# Doorbell.net
KiCad netlist of a schematic drawn in EAGLE
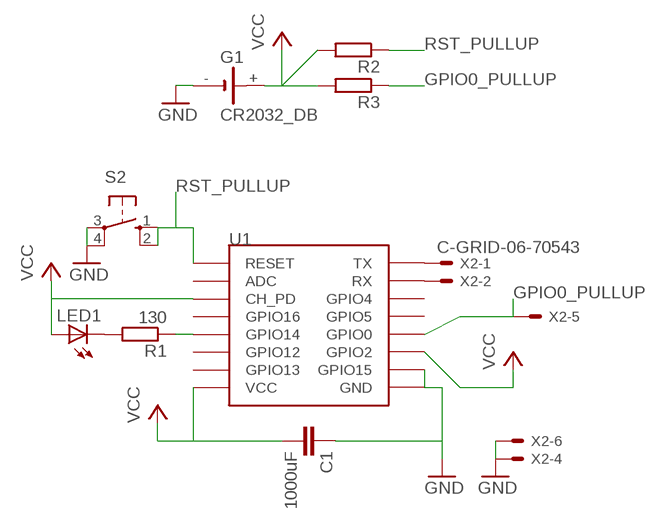
[diagram p0: schematic, sheet 1]

(export (version "E")
  (design (tool "Eeschema 10.0.6"))
  (components
    (comp (ref "C1")
      (value "1000uF")
      (footprint "eagle-import:C5B3.5")
      (libsource (lib "eagle-import") (part "C5/3.5"))
    )
    (comp (ref "G1")
      (value "CR2032_DB")
      (footprint "eagle-import:CR2032_DOORBELL")
      (libsource (lib "eagle-import") (part "CR2032_DB"))
    )
    (comp (ref "LED1")
      (value "LED3MM")
      (footprint "eagle-import:LED3MM")
      (libsource (lib "eagle-import") (part "LED3MM"))
    )
    (comp (ref "R1")
      (value "130")
      (footprint "eagle-import:0204_5")
      (libsource (lib "eagle-import") (part "R-EU_0204/5"))
    )
    (comp (ref "R2")
      (value "R-EU_0204/5")
      (footprint "eagle-import:0204_5")
      (libsource (lib "eagle-import") (part "R-EU_0204/5"))
    )
    (comp (ref "R3")
      (value "R-EU_0204/5")
      (footprint "eagle-import:0204_5")
      (libsource (lib "eagle-import") (part "R-EU_0204/5"))
    )
    (comp (ref "S2")
      (value "10-XX")
      (footprint "eagle-import:B3F-10XX")
      (fields (field (name "MPN") "B3F-1000"))
      (libsource (lib "eagle-import") (part "10-XX"))
    )
    (comp (ref "U1")
      (value "ESP12")
      (footprint "eagle-import:ESP12")
      (libsource (lib "eagle-import") (part "ESP12"))
    )
    (comp (ref "X2")
      (value "C-GRID-06-70543")
      (footprint "eagle-import:70543-06")
      (libsource (lib "eagle-import") (part "C-GRID-06-70543"))
    )
  )
  (nets
    (net (code "1") (name "/GPIO0_PULLUP") (class "Default")
      (node (ref "R3") (pin "1") (pinfunction "1_1") (pintype "passive"))
      (node (ref "U1") (pin "GPIO0") (pinfunction "GPIO0_GPIO0") (pintype "bidirectional"))
      (node (ref "X2") (pin "5") (pinfunction "S_5") (pintype "passive"))
    )
    (net (code "2") (name "/RST_PULLUP") (class "Default")
      (node (ref "R2") (pin "1") (pinfunction "1_1") (pintype "passive"))
      (node (ref "S2") (pin "1") (pinfunction "S_1") (pintype "passive"))
      (node (ref "S2") (pin "2") (pinfunction "S1_2") (pintype "passive"))
      (node (ref "U1") (pin "RESET") (pinfunction "RESET_RESET") (pintype "bidirectional"))
    )
    (net (code "3") (name "GND") (class "Default")
      (node (ref "C1") (pin "1") (pinfunction "1_1") (pintype "passive"))
      (node (ref "G1") (pin "-") (pinfunction "-_-") (pintype "passive"))
      (node (ref "S2") (pin "3") (pinfunction "P_3") (pintype "passive"))
      (node (ref "S2") (pin "4") (pinfunction "P1_4") (pintype "passive"))
      (node (ref "U1") (pin "GND") (pinfunction "GND_GND") (pintype "bidirectional"))
      (node (ref "U1") (pin "GPIO15") (pinfunction "GPIO15_GPIO15") (pintype "bidirectional"))
      (node (ref "X2") (pin "4") (pinfunction "S_4") (pintype "passive"))
      (node (ref "X2") (pin "6") (pinfunction "S_6") (pintype "passive"))
    )
    (net (code "4") (name "Net-(LED1-C)") (class "Default")
      (node (ref "LED1") (pin "K") (pinfunction "C_K") (pintype "passive"))
      (node (ref "R1") (pin "2") (pinfunction "2_2") (pintype "passive"))
    )
    (net (code "5") (name "Net-(R1-Pad1)") (class "Default")
      (node (ref "R1") (pin "1") (pinfunction "1_1") (pintype "passive"))
      (node (ref "U1") (pin "GPIO14") (pinfunction "GPIO14_GPIO14") (pintype "bidirectional"))
    )
    (net (code "6") (name "Net-(X2A-S)") (class "Default")
      (node (ref "U1") (pin "TX") (pinfunction "TX_TX") (pintype "bidirectional"))
      (node (ref "X2") (pin "1") (pinfunction "S_1") (pintype "passive"))
    )
    (net (code "7") (name "Net-(X2B-S)") (class "Default")
      (node (ref "U1") (pin "RX") (pinfunction "RX_RX") (pintype "bidirectional"))
      (node (ref "X2") (pin "2") (pinfunction "S_2") (pintype "passive"))
    )
    (net (code "8") (name "VCC") (class "Default")
      (node (ref "C1") (pin "2") (pinfunction "2_2") (pintype "passive"))
      (node (ref "G1") (pin "+") (pinfunction "+_+") (pintype "passive"))
      (node (ref "LED1") (pin "A") (pinfunction "A_A") (pintype "passive"))
      (node (ref "R2") (pin "2") (pinfunction "2_2") (pintype "passive"))
      (node (ref "R3") (pin "2") (pinfunction "2_2") (pintype "passive"))
      (node (ref "U1") (pin "CH_PD") (pinfunction "CH_PD_CH_PD") (pintype "bidirectional"))
      (node (ref "U1") (pin "GPIO2") (pinfunction "GPIO2_GPIO2") (pintype "bidirectional"))
      (node (ref "U1") (pin "VCC") (pinfunction "VCC_VCC") (pintype "bidirectional"))
    )
    (net (code "9") (name "unconnected-(U1-PadADC)") (class "Default")
      (node (ref "U1") (pin "ADC") (pinfunction "ADC_ADC") (pintype "bidirectional"))
    )
    (net (code "10") (name "unconnected-(U1-PadGPIO4)") (class "Default")
      (node (ref "U1") (pin "GPIO4") (pinfunction "GPIO4_GPIO4") (pintype "bidirectional"))
    )
    (net (code "11") (name "unconnected-(U1-PadGPIO5)") (class "Default")
      (node (ref "U1") (pin "GPIO5") (pinfunction "GPIO5_GPIO5") (pintype "bidirectional"))
    )
    (net (code "12") (name "unconnected-(U1-PadGPIO12)") (class "Default")
      (node (ref "U1") (pin "GPIO12") (pinfunction "GPIO12_GPIO12") (pintype "bidirectional"))
    )
    (net (code "13") (name "unconnected-(U1-PadGPIO13)") (class "Default")
      (node (ref "U1") (pin "GPIO13") (pinfunction "GPIO13_GPIO13") (pintype "bidirectional"))
    )
    (net (code "14") (name "unconnected-(U1-PadGPIO16)") (class "Default")
      (node (ref "U1") (pin "GPIO16") (pinfunction "GPIO16_GPIO16") (pintype "bidirectional"))
    )
  )
)
